# conn_fan.net
KiCad netlist of a schematic drawn in Altium Designer
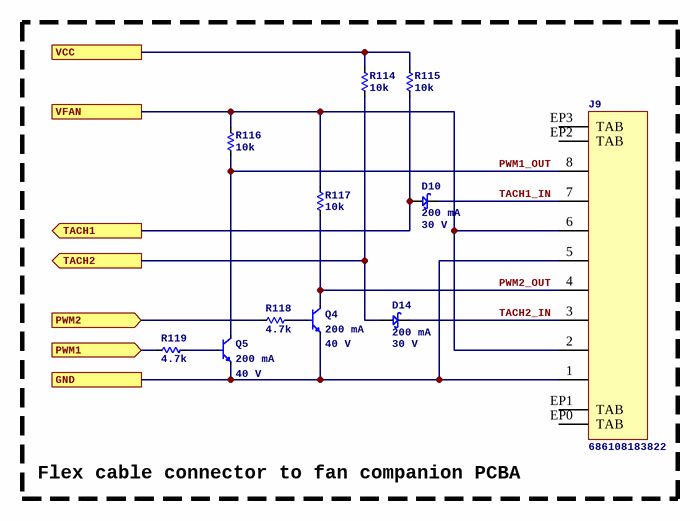
[diagram p0: conn_fan.SchDoc]

(export (version "E")
  (design (tool "Eeschema 10.0.6"))
  (components
    (comp (ref "D10")
      (value "BAT54XV2T1G")
      (footprint "SOD523")
      (description "ON Semi BAT54XV2T1G; SMT Schottky Diode; 30V 200mA; 5ns; 2-Pin SOD-523")
      (fields
        (field (name "MANUFACTURER") "onsemi")
        (field (name "CURRENT") "200 mA")
        (field (name "VOLTAGE") "30 V")
      )
      (libsource (lib "SSCP") (part "SCHOTTKY_30V_BAT54XV2T1G"))
    )
    (comp (ref "D14")
      (value "BAT54XV2T1G")
      (footprint "SOD523")
      (description "ON Semi BAT54XV2T1G; SMT Schottky Diode; 30V 200mA; 5ns; 2-Pin SOD-523")
      (fields
        (field (name "MANUFACTURER") "onsemi")
        (field (name "CURRENT") "200 mA")
        (field (name "VOLTAGE") "30 V")
      )
      (libsource (lib "SSCP") (part "SCHOTTKY_30V_BAT54XV2T1G"))
    )
    (comp (ref "J9")
      (value "686108183822")
      (footprint "WURTH_WR-FPC_1.00mm_686108183822")
      (description "CONN FFC VERT 8POS 1MM SMD")
      (fields (field (name "MANUFACTURER") "Wurth Elektronik"))
      (libsource (lib "SSCP") (part "CONN_WURTH_WR-FPC_8POS_1.00mm_686108183822"))
    )
    (comp (ref "Q4")
      (value "MMBT3904T")
      (footprint "3SOT523")
      (description "Bipolar (BJT) Transistor NPN 40 V 200 mA 300MHz 150 mW Surface Mount SOT-523")
      (fields
        (field (name "MANUFACTURER") "Shenzhen Slkormicro Semicon Co., Ltd.")
        (field (name "CURRENT") "200 mA")
        (field (name "VOLTAGE") "40 V")
      )
      (libsource (lib "SSCP") (part "NPN_40V_MMBT3904T"))
    )
    (comp (ref "Q5")
      (value "MMBT3904T")
      (footprint "3SOT523")
      (description "Bipolar (BJT) Transistor NPN 40 V 200 mA 300MHz 150 mW Surface Mount SOT-523")
      (fields
        (field (name "MANUFACTURER") "Shenzhen Slkormicro Semicon Co., Ltd.")
        (field (name "CURRENT") "200 mA")
        (field (name "VOLTAGE") "40 V")
      )
      (libsource (lib "SSCP") (part "NPN_40V_MMBT3904T"))
    )
    (comp (ref "R114")
      (value "10k")
      (footprint "R0402")
      (fields
        (field (name "TOLERANCE") "1%")
        (field (name "MANUFACTURER PART NUMBER") "0402WGF1002TCE")
        (field (name "MANUFACTURER") "UNI-ROYAL(Uniroyal Elec)")
      )
      (libsource (lib "database") (part "__template_resistor"))
    )
    (comp (ref "R115")
      (value "10k")
      (footprint "R0402")
      (fields
        (field (name "TOLERANCE") "1%")
        (field (name "MANUFACTURER PART NUMBER") "0402WGF1002TCE")
        (field (name "MANUFACTURER") "UNI-ROYAL(Uniroyal Elec)")
      )
      (libsource (lib "database") (part "__template_resistor"))
    )
    (comp (ref "R116")
      (value "10k")
      (footprint "R0402")
      (fields
        (field (name "TOLERANCE") "1%")
        (field (name "MANUFACTURER PART NUMBER") "0402WGF1002TCE")
        (field (name "MANUFACTURER") "UNI-ROYAL(Uniroyal Elec)")
      )
      (libsource (lib "database") (part "__template_resistor"))
    )
    (comp (ref "R117")
      (value "10k")
      (footprint "R0402")
      (fields
        (field (name "TOLERANCE") "1%")
        (field (name "MANUFACTURER PART NUMBER") "0402WGF1002TCE")
        (field (name "MANUFACTURER") "UNI-ROYAL(Uniroyal Elec)")
      )
      (libsource (lib "database") (part "__template_resistor"))
    )
    (comp (ref "R118")
      (value "4.7k")
      (footprint "R0402")
      (fields
        (field (name "TOLERANCE") "1%")
        (field (name "MANUFACTURER PART NUMBER") "0402WGF4701TCE")
        (field (name "MANUFACTURER") "UNI-ROYAL(Uniroyal Elec)")
      )
      (libsource (lib "database") (part "__template_resistor"))
    )
    (comp (ref "R119")
      (value "4.7k")
      (footprint "R0402")
      (fields
        (field (name "TOLERANCE") "1%")
        (field (name "MANUFACTURER PART NUMBER") "0402WGF4701TCE")
        (field (name "MANUFACTURER") "UNI-ROYAL(Uniroyal Elec)")
      )
      (libsource (lib "database") (part "__template_resistor"))
    )
  )
  (nets
    (net (code "1") (name "/GND") (class "Default")
      (node (ref "J9") (pin "1") (pintype "passive"))
      (node (ref "J9") (pin "5") (pintype "passive"))
      (node (ref "Q4") (pin "2") (pinfunction "E_2") (pintype "passive"))
      (node (ref "Q5") (pin "2") (pinfunction "E_2") (pintype "passive"))
    )
    (net (code "2") (name "/PWM1") (class "Default") (node (ref "R119") (pin "2") (pintype "passive")))
    (net (code "3") (name "/PWM1_OUT") (class "Default")
      (node (ref "J9") (pin "8") (pintype "passive"))
      (node (ref "Q5") (pin "3") (pinfunction "C_3") (pintype "passive"))
      (node (ref "R116") (pin "2") (pintype "passive"))
    )
    (net (code "4") (name "/PWM2") (class "Default") (node (ref "R118") (pin "2") (pintype "passive")))
    (net (code "5") (name "/PWM2_OUT") (class "Default")
      (node (ref "J9") (pin "4") (pintype "passive"))
      (node (ref "Q4") (pin "3") (pinfunction "C_3") (pintype "passive"))
      (node (ref "R117") (pin "2") (pintype "passive"))
    )
    (net (code "6") (name "/TACH1") (class "Default")
      (node (ref "D10") (pin "1") (pintype "passive"))
      (node (ref "R115") (pin "2") (pintype "passive"))
    )
    (net (code "7") (name "/TACH1_IN") (class "Default")
      (node (ref "D10") (pin "2") (pintype "passive"))
      (node (ref "J9") (pin "7") (pintype "passive"))
    )
    (net (code "8") (name "/TACH2") (class "Default")
      (node (ref "D14") (pin "1") (pintype "passive"))
      (node (ref "R114") (pin "2") (pintype "passive"))
    )
    (net (code "9") (name "/TACH2_IN") (class "Default")
      (node (ref "D14") (pin "2") (pintype "passive"))
      (node (ref "J9") (pin "3") (pintype "passive"))
    )
    (net (code "10") (name "/VCC") (class "Default")
      (node (ref "R114") (pin "1") (pintype "passive"))
      (node (ref "R115") (pin "1") (pintype "passive"))
    )
    (net (code "11") (name "/VFAN") (class "Default")
      (node (ref "J9") (pin "2") (pintype "passive"))
      (node (ref "J9") (pin "6") (pintype "passive"))
      (node (ref "R116") (pin "1") (pintype "passive"))
      (node (ref "R117") (pin "1") (pintype "passive"))
    )
    (net (code "12") (name "Net-(Q4-B)") (class "Default")
      (node (ref "Q4") (pin "1") (pinfunction "B_1") (pintype "passive"))
      (node (ref "R118") (pin "1") (pintype "passive"))
    )
    (net (code "13") (name "Net-(Q5-B)") (class "Default")
      (node (ref "Q5") (pin "1") (pinfunction "B_1") (pintype "passive"))
      (node (ref "R119") (pin "1") (pintype "passive"))
    )
    (net (code "14") (name "unconnected-(J9-TAB-PadEP0)") (class "Default")
      (node (ref "J9") (pin "EP0") (pinfunction "TAB_EP0") (pintype "passive"))
    )
    (net (code "15") (name "unconnected-(J9-TAB-PadEP1)") (class "Default")
      (node (ref "J9") (pin "EP1") (pinfunction "TAB_EP1") (pintype "passive"))
    )
    (net (code "16") (name "unconnected-(J9-TAB-PadEP2)") (class "Default")
      (node (ref "J9") (pin "EP2") (pinfunction "TAB_EP2") (pintype "passive"))
    )
    (net (code "17") (name "unconnected-(J9-TAB-PadEP3)") (class "Default")
      (node (ref "J9") (pin "EP3") (pinfunction "TAB_EP3") (pintype "passive"))
    )
  )
)
